# untitled.net
KiCad netlist of a schematic drawn in EAGLE
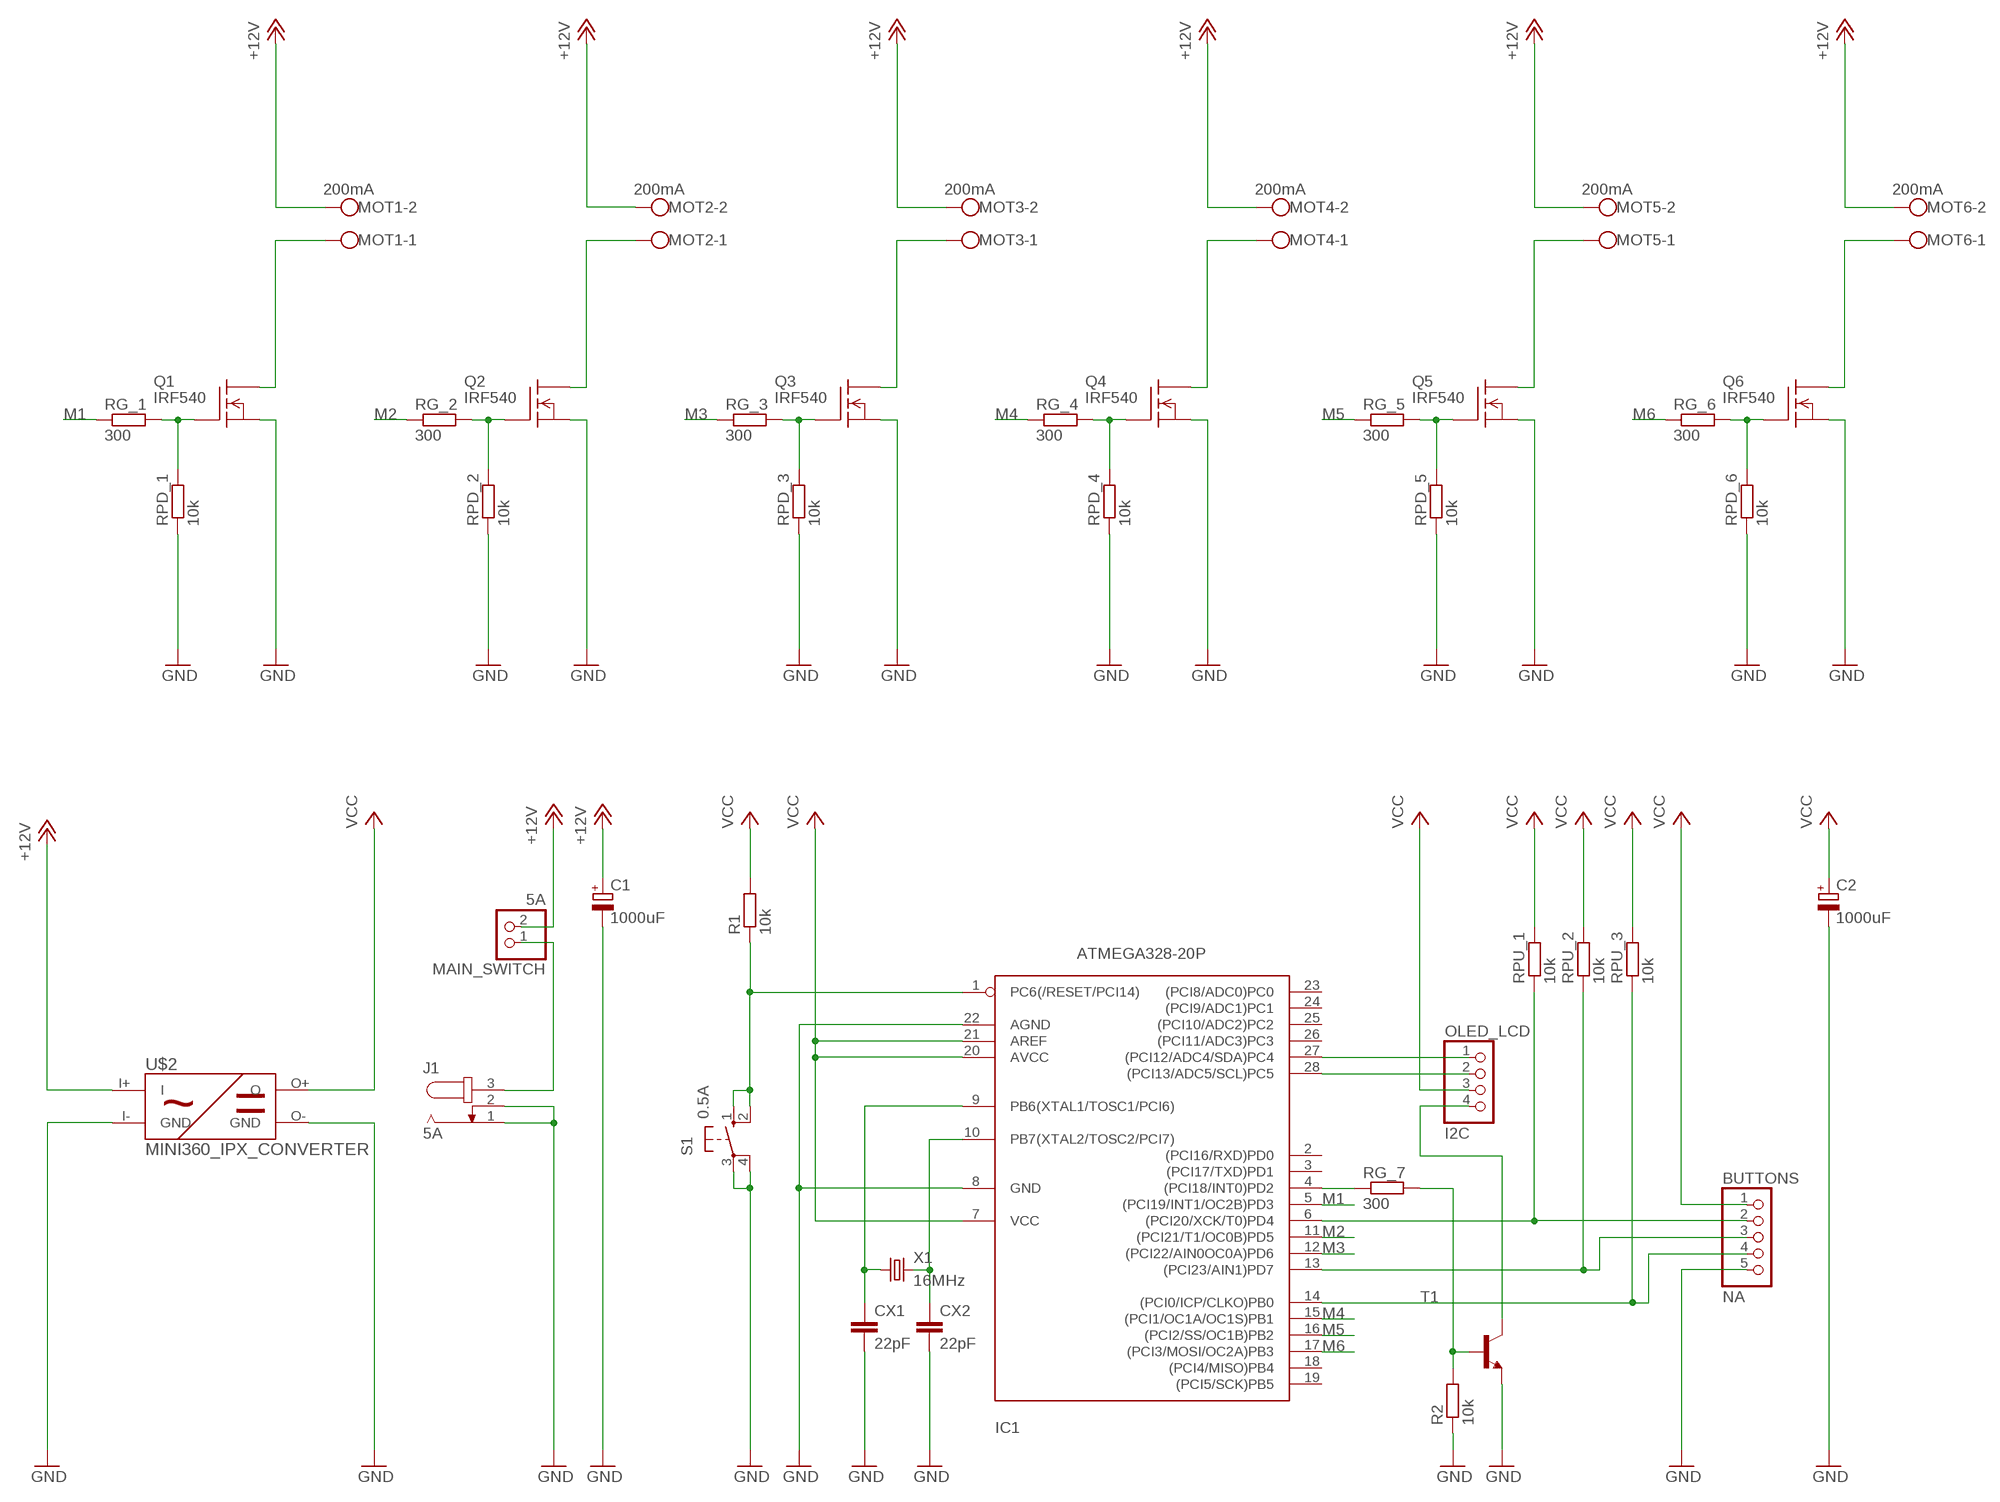
[diagram p0: schematic, sheet 1]

(export (version "E")
  (design (tool "Eeschema 10.0.6"))
  (components
    (comp (ref "BUTTONS")
      (value "NA")
      (footprint "eagle-import:1X05")
      (libsource (lib "eagle-import") (part "PINHD-1X5"))
    )
    (comp (ref "C1")
      (value "1000uF")
      (footprint "eagle-import:E5-8,5")
      (libsource (lib "eagle-import") (part "CPOL-EUE5-8.5"))
    )
    (comp (ref "C2")
      (value "1000uF")
      (footprint "eagle-import:E5-8,5")
      (libsource (lib "eagle-import") (part "CPOL-EUE5-8.5"))
    )
    (comp (ref "CX1")
      (value "22pF")
      (footprint "eagle-import:C025-024X044")
      (libsource (lib "eagle-import") (part "C-EU025-024X044"))
    )
    (comp (ref "CX2")
      (value "22pF")
      (footprint "eagle-import:C025-024X044")
      (libsource (lib "eagle-import") (part "C-EU025-024X044"))
    )
    (comp (ref "IC1")
      (value "ATMEGA328-20P")
      (footprint "eagle-import:DIL28-3")
      (libsource (lib "eagle-import") (part "ATMEGA328P-20"))
    )
    (comp (ref "J1")
      (value "5A")
      (footprint "eagle-import:SPC4078")
      (libsource (lib "eagle-import") (part "JACK-PLUG1"))
    )
    (comp (ref "MAIN_SWITCH")
      (value "5A")
      (footprint "eagle-import:1X02")
      (libsource (lib "eagle-import") (part "PINHD-1X2"))
    )
    (comp (ref "MOT1")
      (value "200mA")
      (footprint "eagle-import:W237-102")
      (fields (field (name "MPN") "237-102"))
      (libsource (lib "eagle-import") (part "W237-102"))
    )
    (comp (ref "MOT2")
      (value "200mA")
      (footprint "eagle-import:W237-102")
      (fields (field (name "MPN") "237-102"))
      (libsource (lib "eagle-import") (part "W237-102"))
    )
    (comp (ref "MOT3")
      (value "200mA")
      (footprint "eagle-import:W237-102")
      (fields (field (name "MPN") "237-102"))
      (libsource (lib "eagle-import") (part "W237-102"))
    )
    (comp (ref "MOT4")
      (value "200mA")
      (footprint "eagle-import:W237-102")
      (fields (field (name "MPN") "237-102"))
      (libsource (lib "eagle-import") (part "W237-102"))
    )
    (comp (ref "MOT5")
      (value "200mA")
      (footprint "eagle-import:W237-102")
      (fields (field (name "MPN") "237-102"))
      (libsource (lib "eagle-import") (part "W237-102"))
    )
    (comp (ref "MOT6")
      (value "200mA")
      (footprint "eagle-import:W237-102")
      (fields (field (name "MPN") "237-102"))
      (libsource (lib "eagle-import") (part "W237-102"))
    )
    (comp (ref "OLED_LCD")
      (value "I2C")
      (footprint "eagle-import:1X04")
      (libsource (lib "eagle-import") (part "PINHD-1X4"))
    )
    (comp (ref "Q1")
      (value "IRF540")
      (footprint "eagle-import:TO220")
      (libsource (lib "eagle-import") (part "IRF540"))
    )
    (comp (ref "Q2")
      (value "IRF540")
      (footprint "eagle-import:TO220")
      (libsource (lib "eagle-import") (part "IRF540"))
    )
    (comp (ref "Q3")
      (value "IRF540")
      (footprint "eagle-import:TO220")
      (libsource (lib "eagle-import") (part "IRF540"))
    )
    (comp (ref "Q4")
      (value "IRF540")
      (footprint "eagle-import:TO220")
      (libsource (lib "eagle-import") (part "IRF540"))
    )
    (comp (ref "Q5")
      (value "IRF540")
      (footprint "eagle-import:TO220")
      (libsource (lib "eagle-import") (part "IRF540"))
    )
    (comp (ref "Q6")
      (value "IRF540")
      (footprint "eagle-import:TO220")
      (libsource (lib "eagle-import") (part "IRF540"))
    )
    (comp (ref "R1")
      (value "10k")
      (footprint "eagle-import:0207_10")
      (libsource (lib "eagle-import") (part "R-EU_0207/10"))
    )
    (comp (ref "R2")
      (value "10k")
      (footprint "eagle-import:0207_10")
      (libsource (lib "eagle-import") (part "R-EU_0207/10"))
    )
    (comp (ref "RG_1")
      (value "300")
      (footprint "eagle-import:0207_10")
      (libsource (lib "eagle-import") (part "R-EU_0207/10"))
    )
    (comp (ref "RG_2")
      (value "300")
      (footprint "eagle-import:0207_10")
      (libsource (lib "eagle-import") (part "R-EU_0207/10"))
    )
    (comp (ref "RG_3")
      (value "300")
      (footprint "eagle-import:0207_10")
      (libsource (lib "eagle-import") (part "R-EU_0207/10"))
    )
    (comp (ref "RG_4")
      (value "300")
      (footprint "eagle-import:0207_10")
      (libsource (lib "eagle-import") (part "R-EU_0207/10"))
    )
    (comp (ref "RG_5")
      (value "300")
      (footprint "eagle-import:0207_10")
      (libsource (lib "eagle-import") (part "R-EU_0207/10"))
    )
    (comp (ref "RG_6")
      (value "300")
      (footprint "eagle-import:0207_10")
      (libsource (lib "eagle-import") (part "R-EU_0207/10"))
    )
    (comp (ref "RG_7")
      (value "300")
      (footprint "eagle-import:0207_10")
      (libsource (lib "eagle-import") (part "R-EU_0207/10"))
    )
    (comp (ref "RPD_1")
      (value "10k")
      (footprint "eagle-import:0207_10")
      (libsource (lib "eagle-import") (part "R-EU_0207/10"))
    )
    (comp (ref "RPD_2")
      (value "10k")
      (footprint "eagle-import:0207_10")
      (libsource (lib "eagle-import") (part "R-EU_0207/10"))
    )
    (comp (ref "RPD_3")
      (value "10k")
      (footprint "eagle-import:0207_10")
      (libsource (lib "eagle-import") (part "R-EU_0207/10"))
    )
    (comp (ref "RPD_4")
      (value "10k")
      (footprint "eagle-import:0207_10")
      (libsource (lib "eagle-import") (part "R-EU_0207/10"))
    )
    (comp (ref "RPD_5")
      (value "10k")
      (footprint "eagle-import:0207_10")
      (libsource (lib "eagle-import") (part "R-EU_0207/10"))
    )
    (comp (ref "RPD_6")
      (value "10k")
      (footprint "eagle-import:0207_10")
      (libsource (lib "eagle-import") (part "R-EU_0207/10"))
    )
    (comp (ref "RPU_1")
      (value "10k")
      (footprint "eagle-import:0207_10")
      (libsource (lib "eagle-import") (part "R-EU_0207/10"))
    )
    (comp (ref "RPU_2")
      (value "10k")
      (footprint "eagle-import:0207_10")
      (libsource (lib "eagle-import") (part "R-EU_0207/10"))
    )
    (comp (ref "RPU_3")
      (value "10k")
      (footprint "eagle-import:0207_10")
      (libsource (lib "eagle-import") (part "R-EU_0207/10"))
    )
    (comp (ref "S1")
      (value "0.5A")
      (footprint "eagle-import:B3F-10XX")
      (fields (field (name "MPN") "B3F-1000"))
      (libsource (lib "eagle-import") (part "10-XX"))
    )
    (comp (ref "T1")
      (value "2N5551-NPN-TO92-CBE")
      (footprint "eagle-import:TO92-CBE")
      (libsource (lib "eagle-import") (part "-NPN-TO92-CBE2N5551"))
    )
    (comp (ref "U$2")
      (value "MINI360_IPX_CONVERTER")
      (footprint "eagle-import:MINI360_IPX_CONVERTER")
      (libsource (lib "eagle-import") (part "MINI360_IPX_CONVERTER"))
    )
    (comp (ref "X1")
      (value "16MHz")
      (footprint "eagle-import:HC49_S")
      (libsource (lib "eagle-import") (part "CRYSTALHC49S"))
    )
  )
  (nets
    (net (code "1") (name "+12V") (class "Default")
      (node (ref "C1") (pin "+") (pinfunction "+_+") (pintype "passive"))
      (node (ref "MAIN_SWITCH") (pin "2") (pinfunction "2_2") (pintype "passive"))
      (node (ref "MOT1") (pin "2") (pinfunction "KL_2") (pintype "passive"))
      (node (ref "MOT2") (pin "2") (pinfunction "KL_2") (pintype "passive"))
      (node (ref "MOT3") (pin "2") (pinfunction "KL_2") (pintype "passive"))
      (node (ref "MOT4") (pin "2") (pinfunction "KL_2") (pintype "passive"))
      (node (ref "MOT5") (pin "2") (pinfunction "KL_2") (pintype "passive"))
      (node (ref "MOT6") (pin "2") (pinfunction "KL_2") (pintype "passive"))
      (node (ref "U$2") (pin "I+") (pinfunction "I_I+") (pintype "bidirectional"))
    )
    (net (code "2") (name "/M1") (class "Default")
      (node (ref "IC1") (pin "5") (pinfunction "(PCI19/INT1/OC2B)PD3_5") (pintype "bidirectional"))
      (node (ref "RG_1") (pin "1") (pinfunction "1_1") (pintype "passive"))
    )
    (net (code "3") (name "/M2") (class "Default")
      (node (ref "IC1") (pin "11") (pinfunction "(PCI21/T1/OC0B)PD5_11") (pintype "bidirectional"))
      (node (ref "RG_2") (pin "1") (pinfunction "1_1") (pintype "passive"))
    )
    (net (code "4") (name "/M3") (class "Default")
      (node (ref "IC1") (pin "12") (pinfunction "(PCI22/AIN0OC0A)PD6_12") (pintype "bidirectional"))
      (node (ref "RG_3") (pin "1") (pinfunction "1_1") (pintype "passive"))
    )
    (net (code "5") (name "/M4") (class "Default")
      (node (ref "IC1") (pin "15") (pinfunction "(PCI1/OC1A/OC1S)PB1_15") (pintype "bidirectional"))
      (node (ref "RG_4") (pin "1") (pinfunction "1_1") (pintype "passive"))
    )
    (net (code "6") (name "/M5") (class "Default")
      (node (ref "IC1") (pin "16") (pinfunction "(PCI2/SS/OC1B)PB2_16") (pintype "bidirectional"))
      (node (ref "RG_5") (pin "1") (pinfunction "1_1") (pintype "passive"))
    )
    (net (code "7") (name "/M6") (class "Default")
      (node (ref "IC1") (pin "17") (pinfunction "(PCI3/MOSI/OC2A)PB3_17") (pintype "bidirectional"))
      (node (ref "RG_6") (pin "1") (pinfunction "1_1") (pintype "passive"))
    )
    (net (code "8") (name "GND") (class "Default")
      (node (ref "BUTTONS") (pin "5") (pinfunction "5_5") (pintype "passive"))
      (node (ref "C1") (pin "-") (pinfunction "-_-") (pintype "passive"))
      (node (ref "C2") (pin "-") (pinfunction "-_-") (pintype "passive"))
      (node (ref "CX1") (pin "2") (pinfunction "2_2") (pintype "passive"))
      (node (ref "CX2") (pin "2") (pinfunction "2_2") (pintype "passive"))
      (node (ref "IC1") (pin "22") (pinfunction "AGND_22") (pintype "bidirectional"))
      (node (ref "IC1") (pin "8") (pinfunction "GND_8") (pintype "bidirectional"))
      (node (ref "J1") (pin "1") (pinfunction "1_1") (pintype "passive"))
      (node (ref "J1") (pin "2") (pinfunction "2_2") (pintype "passive"))
      (node (ref "Q1") (pin "3") (pinfunction "S_3") (pintype "passive"))
      (node (ref "Q2") (pin "3") (pinfunction "S_3") (pintype "passive"))
      (node (ref "Q3") (pin "3") (pinfunction "S_3") (pintype "passive"))
      (node (ref "Q4") (pin "3") (pinfunction "S_3") (pintype "passive"))
      (node (ref "Q5") (pin "3") (pinfunction "S_3") (pintype "passive"))
      (node (ref "Q6") (pin "3") (pinfunction "S_3") (pintype "passive"))
      (node (ref "R2") (pin "1") (pinfunction "1_1") (pintype "passive"))
      (node (ref "RPD_1") (pin "1") (pinfunction "1_1") (pintype "passive"))
      (node (ref "RPD_2") (pin "1") (pinfunction "1_1") (pintype "passive"))
      (node (ref "RPD_3") (pin "1") (pinfunction "1_1") (pintype "passive"))
      (node (ref "RPD_4") (pin "1") (pinfunction "1_1") (pintype "passive"))
      (node (ref "RPD_5") (pin "1") (pinfunction "1_1") (pintype "passive"))
      (node (ref "RPD_6") (pin "1") (pinfunction "1_1") (pintype "passive"))
      (node (ref "S1") (pin "3") (pinfunction "P_3") (pintype "passive"))
      (node (ref "S1") (pin "4") (pinfunction "P1_4") (pintype "passive"))
      (node (ref "T1") (pin "E") (pinfunction "E_E") (pintype "passive"))
      (node (ref "U$2") (pin "I-") (pinfunction "GND_I-") (pintype "bidirectional"))
      (node (ref "U$2") (pin "O-") (pinfunction "GND_O-") (pintype "bidirectional"))
    )
    (net (code "9") (name "Net-(IC1-(PCI0{slash}ICP{slash}CLKO)PB0)") (class "Default")
      (node (ref "BUTTONS") (pin "4") (pinfunction "4_4") (pintype "passive"))
      (node (ref "IC1") (pin "14") (pinfunction "(PCI0/ICP/CLKO)PB0_14") (pintype "bidirectional"))
      (node (ref "RPU_3") (pin "1") (pinfunction "1_1") (pintype "passive"))
    )
    (net (code "10") (name "Net-(IC1-(PCI12{slash}ADC4{slash}SDA)PC4)") (class "Default")
      (node (ref "IC1") (pin "27") (pinfunction "(PCI12/ADC4/SDA)PC4_27") (pintype "bidirectional"))
      (node (ref "OLED_LCD") (pin "1") (pinfunction "1_1") (pintype "passive"))
    )
    (net (code "11") (name "Net-(IC1-(PCI13{slash}ADC5{slash}SCL)PC5)") (class "Default")
      (node (ref "IC1") (pin "28") (pinfunction "(PCI13/ADC5/SCL)PC5_28") (pintype "bidirectional"))
      (node (ref "OLED_LCD") (pin "2") (pinfunction "2_2") (pintype "passive"))
    )
    (net (code "12") (name "Net-(IC1-(PCI18{slash}INT0)PD2)") (class "Default")
      (node (ref "IC1") (pin "4") (pinfunction "(PCI18/INT0)PD2_4") (pintype "bidirectional"))
      (node (ref "RG_7") (pin "1") (pinfunction "1_1") (pintype "passive"))
    )
    (net (code "13") (name "Net-(IC1-(PCI20{slash}XCK{slash}T0)PD4)") (class "Default")
      (node (ref "BUTTONS") (pin "2") (pinfunction "2_2") (pintype "passive"))
      (node (ref "IC1") (pin "6") (pinfunction "(PCI20/XCK/T0)PD4_6") (pintype "bidirectional"))
      (node (ref "RPU_1") (pin "1") (pinfunction "1_1") (pintype "passive"))
    )
    (net (code "14") (name "Net-(IC1-(PCI23{slash}AIN1)PD7)") (class "Default")
      (node (ref "BUTTONS") (pin "3") (pinfunction "3_3") (pintype "passive"))
      (node (ref "IC1") (pin "13") (pinfunction "(PCI23/AIN1)PD7_13") (pintype "bidirectional"))
      (node (ref "RPU_2") (pin "1") (pinfunction "1_1") (pintype "passive"))
    )
    (net (code "15") (name "Net-(IC1-PB6(XTAL1{slash}TOSC1{slash}PCI6))") (class "Default")
      (node (ref "CX1") (pin "1") (pinfunction "1_1") (pintype "passive"))
      (node (ref "IC1") (pin "9") (pinfunction "PB6(XTAL1/TOSC1/PCI6)_9") (pintype "bidirectional"))
      (node (ref "X1") (pin "1") (pinfunction "1_1") (pintype "passive"))
    )
    (net (code "16") (name "Net-(IC1-PB7(XTAL2{slash}TOSC2{slash}PCI7))") (class "Default")
      (node (ref "CX2") (pin "1") (pinfunction "1_1") (pintype "passive"))
      (node (ref "IC1") (pin "10") (pinfunction "PB7(XTAL2/TOSC2/PCI7)_10") (pintype "bidirectional"))
      (node (ref "X1") (pin "2") (pinfunction "2_2") (pintype "passive"))
    )
    (net (code "17") (name "Net-(IC1-PC6({slash}RESET{slash}PCI14))") (class "Default")
      (node (ref "IC1") (pin "1") (pinfunction "PC6(/RESET/PCI14)_1") (pintype "bidirectional"))
      (node (ref "R1") (pin "1") (pinfunction "1_1") (pintype "passive"))
      (node (ref "S1") (pin "1") (pinfunction "S_1") (pintype "passive"))
      (node (ref "S1") (pin "2") (pinfunction "S1_2") (pintype "passive"))
    )
    (net (code "18") (name "Net-(J1-Pad3)") (class "Default")
      (node (ref "J1") (pin "3") (pinfunction "3_3") (pintype "passive"))
      (node (ref "MAIN_SWITCH") (pin "1") (pinfunction "1_1") (pintype "passive"))
    )
    (net (code "19") (name "Net-(MOT1A-KL)") (class "Default")
      (node (ref "MOT1") (pin "1") (pinfunction "KL_1") (pintype "passive"))
      (node (ref "Q1") (pin "2") (pinfunction "D_2") (pintype "passive"))
    )
    (net (code "20") (name "Net-(MOT2A-KL)") (class "Default")
      (node (ref "MOT2") (pin "1") (pinfunction "KL_1") (pintype "passive"))
      (node (ref "Q2") (pin "2") (pinfunction "D_2") (pintype "passive"))
    )
    (net (code "21") (name "Net-(MOT3A-KL)") (class "Default")
      (node (ref "MOT3") (pin "1") (pinfunction "KL_1") (pintype "passive"))
      (node (ref "Q3") (pin "2") (pinfunction "D_2") (pintype "passive"))
    )
    (net (code "22") (name "Net-(MOT4A-KL)") (class "Default")
      (node (ref "MOT4") (pin "1") (pinfunction "KL_1") (pintype "passive"))
      (node (ref "Q4") (pin "2") (pinfunction "D_2") (pintype "passive"))
    )
    (net (code "23") (name "Net-(MOT5A-KL)") (class "Default")
      (node (ref "MOT5") (pin "1") (pinfunction "KL_1") (pintype "passive"))
      (node (ref "Q5") (pin "2") (pinfunction "D_2") (pintype "passive"))
    )
    (net (code "24") (name "Net-(MOT6A-KL)") (class "Default")
      (node (ref "MOT6") (pin "1") (pinfunction "KL_1") (pintype "passive"))
      (node (ref "Q6") (pin "2") (pinfunction "D_2") (pintype "passive"))
    )
    (net (code "25") (name "Net-(OLED_LCD-Pad4)") (class "Default")
      (node (ref "OLED_LCD") (pin "4") (pinfunction "4_4") (pintype "passive"))
      (node (ref "T1") (pin "C") (pinfunction "C_C") (pintype "passive"))
    )
    (net (code "26") (name "Net-(Q1-G)") (class "Default")
      (node (ref "Q1") (pin "1") (pinfunction "G_1") (pintype "passive"))
      (node (ref "RG_1") (pin "2") (pinfunction "2_2") (pintype "passive"))
      (node (ref "RPD_1") (pin "2") (pinfunction "2_2") (pintype "passive"))
    )
    (net (code "27") (name "Net-(Q2-G)") (class "Default")
      (node (ref "Q2") (pin "1") (pinfunction "G_1") (pintype "passive"))
      (node (ref "RG_2") (pin "2") (pinfunction "2_2") (pintype "passive"))
      (node (ref "RPD_2") (pin "2") (pinfunction "2_2") (pintype "passive"))
    )
    (net (code "28") (name "Net-(Q3-G)") (class "Default")
      (node (ref "Q3") (pin "1") (pinfunction "G_1") (pintype "passive"))
      (node (ref "RG_3") (pin "2") (pinfunction "2_2") (pintype "passive"))
      (node (ref "RPD_3") (pin "2") (pinfunction "2_2") (pintype "passive"))
    )
    (net (code "29") (name "Net-(Q4-G)") (class "Default")
      (node (ref "Q4") (pin "1") (pinfunction "G_1") (pintype "passive"))
      (node (ref "RG_4") (pin "2") (pinfunction "2_2") (pintype "passive"))
      (node (ref "RPD_4") (pin "2") (pinfunction "2_2") (pintype "passive"))
    )
    (net (code "30") (name "Net-(Q5-G)") (class "Default")
      (node (ref "Q5") (pin "1") (pinfunction "G_1") (pintype "passive"))
      (node (ref "RG_5") (pin "2") (pinfunction "2_2") (pintype "passive"))
      (node (ref "RPD_5") (pin "2") (pinfunction "2_2") (pintype "passive"))
    )
    (net (code "31") (name "Net-(Q6-G)") (class "Default")
      (node (ref "Q6") (pin "1") (pinfunction "G_1") (pintype "passive"))
      (node (ref "RG_6") (pin "2") (pinfunction "2_2") (pintype "passive"))
      (node (ref "RPD_6") (pin "2") (pinfunction "2_2") (pintype "passive"))
    )
    (net (code "32") (name "Net-(R2-Pad2)") (class "Default")
      (node (ref "R2") (pin "2") (pinfunction "2_2") (pintype "passive"))
      (node (ref "RG_7") (pin "2") (pinfunction "2_2") (pintype "passive"))
      (node (ref "T1") (pin "B") (pinfunction "B_B") (pintype "passive"))
    )
    (net (code "33") (name "VCC") (class "Default")
      (node (ref "BUTTONS") (pin "1") (pinfunction "1_1") (pintype "passive"))
      (node (ref "C2") (pin "+") (pinfunction "+_+") (pintype "passive"))
      (node (ref "IC1") (pin "20") (pinfunction "AVCC_20") (pintype "bidirectional"))
      (node (ref "IC1") (pin "21") (pinfunction "AREF_21") (pintype "bidirectional"))
      (node (ref "IC1") (pin "7") (pinfunction "VCC_7") (pintype "bidirectional"))
      (node (ref "OLED_LCD") (pin "3") (pinfunction "3_3") (pintype "passive"))
      (node (ref "R1") (pin "2") (pinfunction "2_2") (pintype "passive"))
      (node (ref "RPU_1") (pin "2") (pinfunction "2_2") (pintype "passive"))
      (node (ref "RPU_2") (pin "2") (pinfunction "2_2") (pintype "passive"))
      (node (ref "RPU_3") (pin "2") (pinfunction "2_2") (pintype "passive"))
      (node (ref "U$2") (pin "O+") (pinfunction "O_O+") (pintype "bidirectional"))
    )
    (net (code "34") (name "unconnected-(IC1-(PCI4{slash}MISO)PB4-Pad18)") (class "Default")
      (node (ref "IC1") (pin "18") (pinfunction "(PCI4/MISO)PB4_18") (pintype "bidirectional"))
    )
    (net (code "35") (name "unconnected-(IC1-(PCI5{slash}SCK)PB5-Pad19)") (class "Default")
      (node (ref "IC1") (pin "19") (pinfunction "(PCI5/SCK)PB5_19") (pintype "bidirectional"))
    )
    (net (code "36") (name "unconnected-(IC1-(PCI8{slash}ADC0)PC0-Pad23)") (class "Default")
      (node (ref "IC1") (pin "23") (pinfunction "(PCI8/ADC0)PC0_23") (pintype "bidirectional"))
    )
    (net (code "37") (name "unconnected-(IC1-(PCI9{slash}ADC1)PC1-Pad24)") (class "Default")
      (node (ref "IC1") (pin "24") (pinfunction "(PCI9/ADC1)PC1_24") (pintype "bidirectional"))
    )
    (net (code "38") (name "unconnected-(IC1-(PCI10{slash}ADC2)PC2-Pad25)") (class "Default")
      (node (ref "IC1") (pin "25") (pinfunction "(PCI10/ADC2)PC2_25") (pintype "bidirectional"))
    )
    (net (code "39") (name "unconnected-(IC1-(PCI11{slash}ADC3)PC3-Pad26)") (class "Default")
      (node (ref "IC1") (pin "26") (pinfunction "(PCI11/ADC3)PC3_26") (pintype "bidirectional"))
    )
    (net (code "40") (name "unconnected-(IC1-(PCI16{slash}RXD)PD0-Pad2)") (class "Default")
      (node (ref "IC1") (pin "2") (pinfunction "(PCI16/RXD)PD0_2") (pintype "bidirectional"))
    )
    (net (code "41") (name "unconnected-(IC1-(PCI17{slash}TXD)PD1-Pad3)") (class "Default")
      (node (ref "IC1") (pin "3") (pinfunction "(PCI17/TXD)PD1_3") (pintype "bidirectional"))
    )
  )
)
